# rapidshark-display-butt-mk-1_1.net
KiCad netlist of a schematic drawn in EAGLE
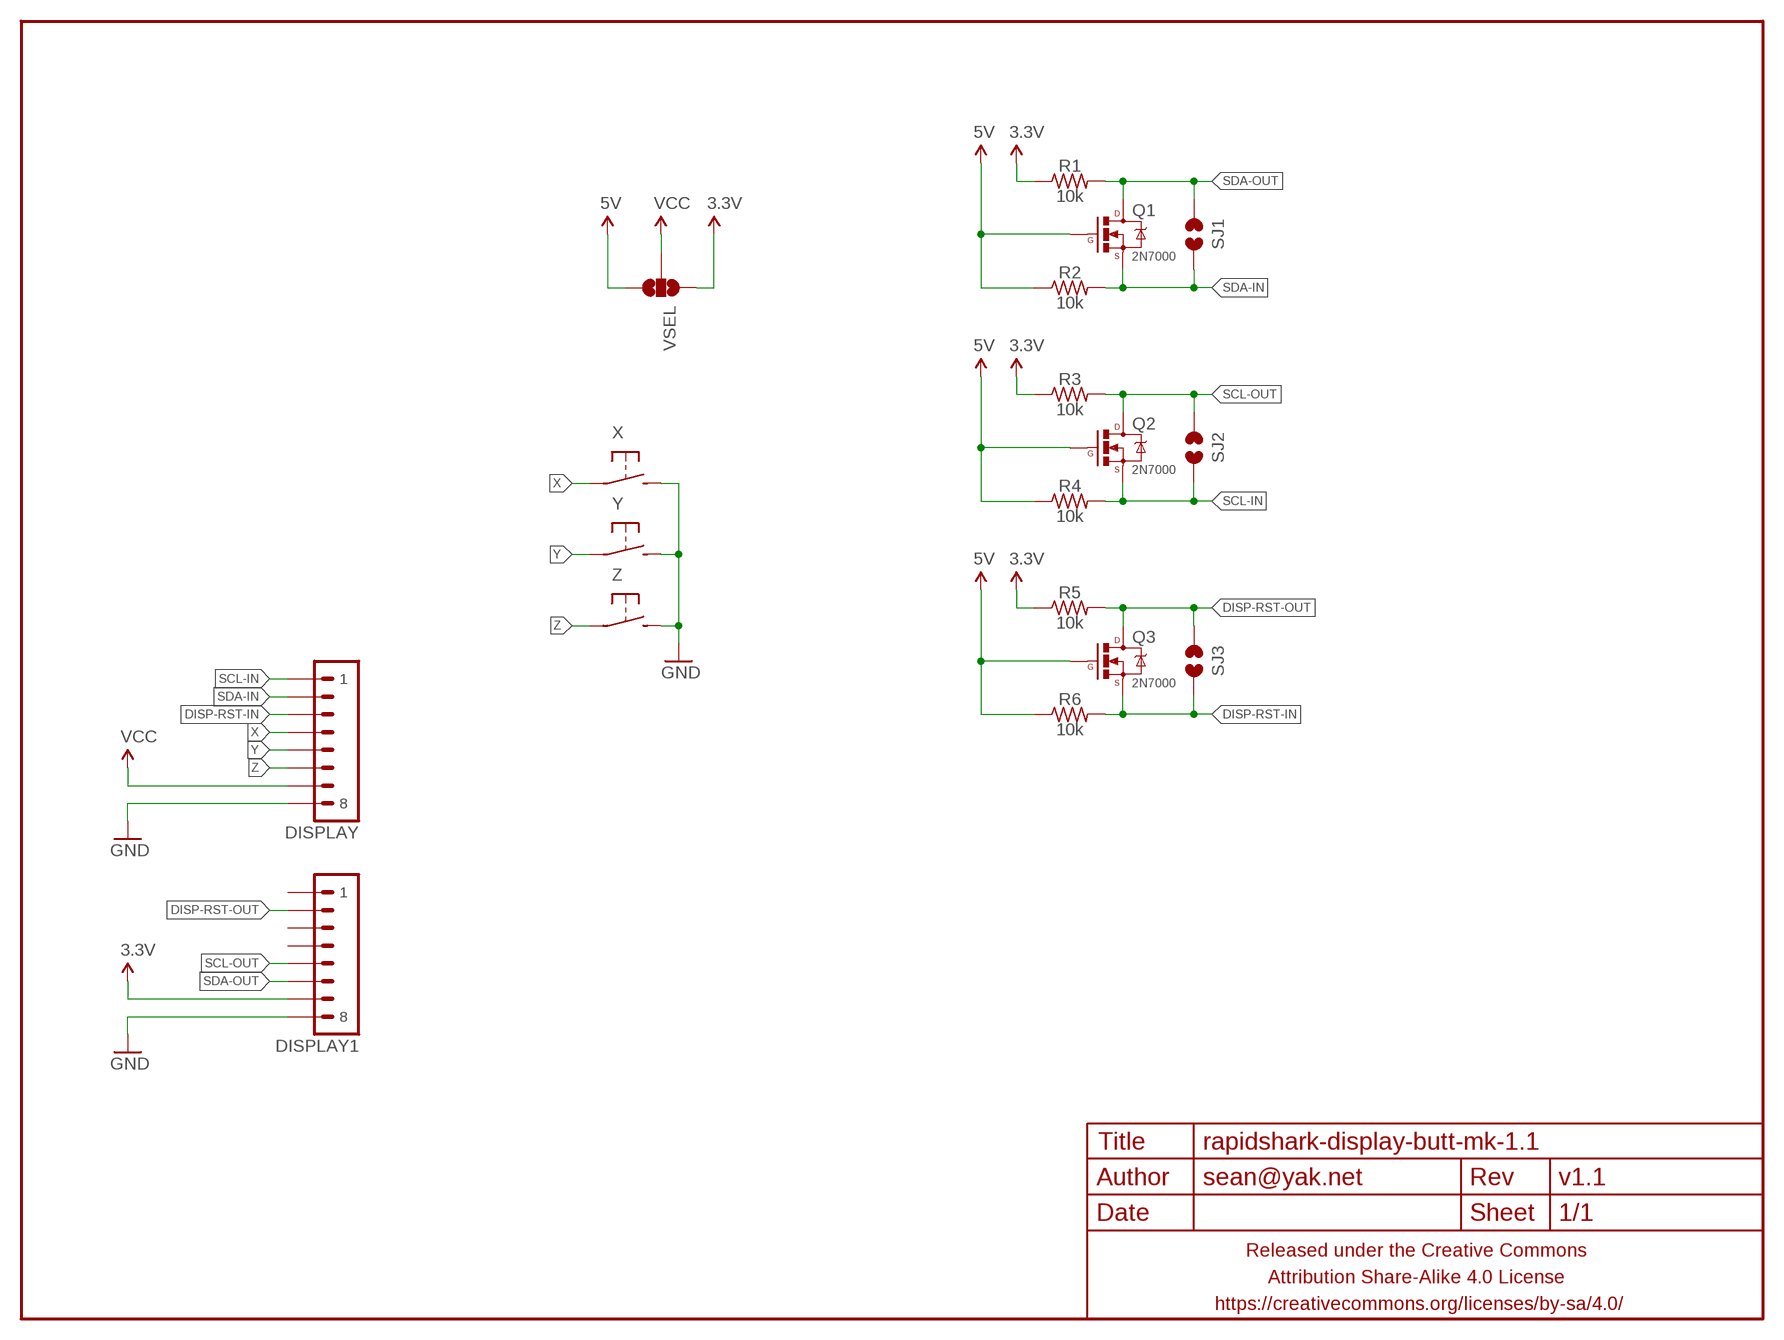
[diagram p0: schematic, sheet 1]

(export (version "E")
  (design (tool "Eeschema 10.0.6"))
  (components
    (comp (ref "DISPLAY")
      (value "M08JST-PH-VERT-PTH")
      (footprint "eagle-import:JST-8-VERT-PTH")
      (libsource (lib "eagle-import") (part "M08JST-PH-VERT-PTH"))
    )
    (comp (ref "DISPLAY1")
      (value "M081X08")
      (footprint "eagle-import:1X08")
      (libsource (lib "eagle-import") (part "M081X08"))
    )
    (comp (ref "FRAME1")
      (value "FRAME-LETTERNO_PACKAGE")
      (footprint "eagle-import:DUMMY")
      (fields (field (name "DESIGNER") "sean@yak.net") (field (name "VERSION") "v1.1"))
      (libsource (lib "eagle-import") (part "FRAME-LETTERNO_PACKAGE"))
    )
    (comp (ref "Q1")
      (value "2N7000")
      (footprint "eagle-import:TO-92-AMMO")
      (libsource (lib "eagle-import") (part "MOSFET-NCHANNEL2N7000-AMMO"))
    )
    (comp (ref "Q2")
      (value "2N7000")
      (footprint "eagle-import:TO-92-AMMO")
      (libsource (lib "eagle-import") (part "MOSFET-NCHANNEL2N7000-AMMO"))
    )
    (comp (ref "Q3")
      (value "2N7000")
      (footprint "eagle-import:TO-92-AMMO")
      (libsource (lib "eagle-import") (part "MOSFET-NCHANNEL2N7000-AMMO"))
    )
    (comp (ref "R1")
      (value "10k")
      (footprint "eagle-import:RESISTOR-AXIAL-PTH-5.08MM")
      (libsource (lib "eagle-import") (part "RESISTORPTH-AXIAL-5.08MM"))
    )
    (comp (ref "R2")
      (value "10k")
      (footprint "eagle-import:RESISTOR-AXIAL-PTH-5.08MM")
      (libsource (lib "eagle-import") (part "RESISTORPTH-AXIAL-5.08MM"))
    )
    (comp (ref "R3")
      (value "10k")
      (footprint "eagle-import:RESISTOR-AXIAL-PTH-5.08MM")
      (libsource (lib "eagle-import") (part "RESISTORPTH-AXIAL-5.08MM"))
    )
    (comp (ref "R4")
      (value "10k")
      (footprint "eagle-import:RESISTOR-AXIAL-PTH-5.08MM")
      (libsource (lib "eagle-import") (part "RESISTORPTH-AXIAL-5.08MM"))
    )
    (comp (ref "R5")
      (value "10k")
      (footprint "eagle-import:RESISTOR-AXIAL-PTH-5.08MM")
      (libsource (lib "eagle-import") (part "RESISTORPTH-AXIAL-5.08MM"))
    )
    (comp (ref "R6")
      (value "10k")
      (footprint "eagle-import:RESISTOR-AXIAL-PTH-5.08MM")
      (libsource (lib "eagle-import") (part "RESISTORPTH-AXIAL-5.08MM"))
    )
    (comp (ref "SJ1")
      (value "JUMPER-PAD-2-NOYES_SILK")
      (footprint "eagle-import:PAD-JUMPER-2-NO_YES_SILK")
      (libsource (lib "eagle-import") (part "JUMPER-PAD-2-NOYES_SILK"))
    )
    (comp (ref "SJ2")
      (value "JUMPER-PAD-2-NOYES_SILK")
      (footprint "eagle-import:PAD-JUMPER-2-NO_YES_SILK")
      (libsource (lib "eagle-import") (part "JUMPER-PAD-2-NOYES_SILK"))
    )
    (comp (ref "SJ3")
      (value "JUMPER-PAD-2-NOYES_SILK")
      (footprint "eagle-import:PAD-JUMPER-2-NO_YES_SILK")
      (libsource (lib "eagle-import") (part "JUMPER-PAD-2-NOYES_SILK"))
    )
    (comp (ref "VSEL")
      (value "JUMPER-PAD-3-NOFULL_BOX_SILK")
      (footprint "eagle-import:PAD-JUMPER-3-NO_YES_SILK_FULL_BOX")
      (libsource (lib "eagle-import") (part "JUMPER-PAD-3-NOFULL_BOX_SILK"))
    )
    (comp (ref "X")
      (value "SPST-NO-TACT6MM-PTH-SMALL-PADS")
      (footprint "eagle-import:DTS-6-SMALL-PADS")
      (libsource (lib "eagle-import") (part "SPST-NO-TACT6MM-PTH-SMALL-PADS"))
    )
    (comp (ref "Y")
      (value "SPST-NO-TACT6MM-PTH-SMALL-PADS")
      (footprint "eagle-import:DTS-6-SMALL-PADS")
      (libsource (lib "eagle-import") (part "SPST-NO-TACT6MM-PTH-SMALL-PADS"))
    )
    (comp (ref "Z")
      (value "SPST-NO-TACT6MM-PTH-SMALL-PADS")
      (footprint "eagle-import:DTS-6-SMALL-PADS")
      (libsource (lib "eagle-import") (part "SPST-NO-TACT6MM-PTH-SMALL-PADS"))
    )
  )
  (nets
    (net (code "1") (name "3.3V") (class "Default")
      (node (ref "DISPLAY1") (pin "7") (pinfunction "7_7") (pintype "passive"))
      (node (ref "R1") (pin "P$1") (pinfunction "1_P$1") (pintype "passive"))
      (node (ref "R3") (pin "P$1") (pinfunction "1_P$1") (pintype "passive"))
      (node (ref "R5") (pin "P$1") (pinfunction "1_P$1") (pintype "passive"))
      (node (ref "VSEL") (pin "1") (pinfunction "1_1") (pintype "passive"))
    )
    (net (code "2") (name "5V") (class "Default")
      (node (ref "Q1") (pin "2") (pinfunction "G_2") (pintype "passive"))
      (node (ref "Q2") (pin "2") (pinfunction "G_2") (pintype "passive"))
      (node (ref "Q3") (pin "2") (pinfunction "G_2") (pintype "passive"))
      (node (ref "R2") (pin "P$1") (pinfunction "1_P$1") (pintype "passive"))
      (node (ref "R4") (pin "P$1") (pinfunction "1_P$1") (pintype "passive"))
      (node (ref "R6") (pin "P$1") (pinfunction "1_P$1") (pintype "passive"))
      (node (ref "VSEL") (pin "3") (pinfunction "3_3") (pintype "passive"))
    )
    (net (code "3") (name "DISP-RST-IN") (class "Default")
      (node (ref "DISPLAY") (pin "3") (pinfunction "3_3") (pintype "passive"))
      (node (ref "Q3") (pin "1") (pinfunction "S_1") (pintype "passive"))
      (node (ref "R6") (pin "P$2") (pinfunction "2_P$2") (pintype "passive"))
      (node (ref "SJ3") (pin "1") (pinfunction "1_1") (pintype "passive"))
    )
    (net (code "4") (name "DISP-RST-OUT") (class "Default")
      (node (ref "DISPLAY1") (pin "2") (pinfunction "2_2") (pintype "passive"))
      (node (ref "Q3") (pin "3") (pinfunction "D_3") (pintype "passive"))
      (node (ref "R5") (pin "P$2") (pinfunction "2_P$2") (pintype "passive"))
      (node (ref "SJ3") (pin "2") (pinfunction "2_2") (pintype "passive"))
    )
    (net (code "5") (name "GND") (class "Default")
      (node (ref "DISPLAY") (pin "8") (pinfunction "8_8") (pintype "passive"))
      (node (ref "DISPLAY1") (pin "8") (pinfunction "8_8") (pintype "passive"))
      (node (ref "X") (pin "3") (pinfunction "2_3") (pintype "passive"))
      (node (ref "X") (pin "4") (pinfunction "2_4") (pintype "passive"))
      (node (ref "Y") (pin "3") (pinfunction "2_3") (pintype "passive"))
      (node (ref "Y") (pin "4") (pinfunction "2_4") (pintype "passive"))
      (node (ref "Z") (pin "3") (pinfunction "2_3") (pintype "passive"))
      (node (ref "Z") (pin "4") (pinfunction "2_4") (pintype "passive"))
    )
    (net (code "6") (name "SCL-IN") (class "Default")
      (node (ref "DISPLAY") (pin "1") (pinfunction "1_1") (pintype "passive"))
      (node (ref "Q2") (pin "1") (pinfunction "S_1") (pintype "passive"))
      (node (ref "R4") (pin "P$2") (pinfunction "2_P$2") (pintype "passive"))
      (node (ref "SJ2") (pin "1") (pinfunction "1_1") (pintype "passive"))
    )
    (net (code "7") (name "SCL-OUT") (class "Default")
      (node (ref "DISPLAY1") (pin "5") (pinfunction "5_5") (pintype "passive"))
      (node (ref "Q2") (pin "3") (pinfunction "D_3") (pintype "passive"))
      (node (ref "R3") (pin "P$2") (pinfunction "2_P$2") (pintype "passive"))
      (node (ref "SJ2") (pin "2") (pinfunction "2_2") (pintype "passive"))
    )
    (net (code "8") (name "SDA-IN") (class "Default")
      (node (ref "DISPLAY") (pin "2") (pinfunction "2_2") (pintype "passive"))
      (node (ref "Q1") (pin "1") (pinfunction "S_1") (pintype "passive"))
      (node (ref "R2") (pin "P$2") (pinfunction "2_P$2") (pintype "passive"))
      (node (ref "SJ1") (pin "1") (pinfunction "1_1") (pintype "passive"))
    )
    (net (code "9") (name "SDA-OUT") (class "Default")
      (node (ref "DISPLAY1") (pin "6") (pinfunction "6_6") (pintype "passive"))
      (node (ref "Q1") (pin "3") (pinfunction "D_3") (pintype "passive"))
      (node (ref "R1") (pin "P$2") (pinfunction "2_P$2") (pintype "passive"))
      (node (ref "SJ1") (pin "2") (pinfunction "2_2") (pintype "passive"))
    )
    (net (code "10") (name "VCC") (class "Default")
      (node (ref "DISPLAY") (pin "7") (pinfunction "7_7") (pintype "passive"))
      (node (ref "VSEL") (pin "2") (pinfunction "2_2") (pintype "passive"))
    )
    (net (code "11") (name "X") (class "Default")
      (node (ref "DISPLAY") (pin "4") (pinfunction "4_4") (pintype "passive"))
      (node (ref "X") (pin "1") (pinfunction "1_1") (pintype "passive"))
      (node (ref "X") (pin "2") (pinfunction "1_2") (pintype "passive"))
    )
    (net (code "12") (name "Y") (class "Default")
      (node (ref "DISPLAY") (pin "5") (pinfunction "5_5") (pintype "passive"))
      (node (ref "Y") (pin "1") (pinfunction "1_1") (pintype "passive"))
      (node (ref "Y") (pin "2") (pinfunction "1_2") (pintype "passive"))
    )
    (net (code "13") (name "Z") (class "Default")
      (node (ref "DISPLAY") (pin "6") (pinfunction "6_6") (pintype "passive"))
      (node (ref "Z") (pin "1") (pinfunction "1_1") (pintype "passive"))
      (node (ref "Z") (pin "2") (pinfunction "1_2") (pintype "passive"))
    )
    (net (code "14") (name "unconnected-(DISPLAY1-Pad1)") (class "Default")
      (node (ref "DISPLAY1") (pin "1") (pinfunction "1_1") (pintype "passive"))
    )
    (net (code "15") (name "unconnected-(DISPLAY1-Pad3)") (class "Default")
      (node (ref "DISPLAY1") (pin "3") (pinfunction "3_3") (pintype "passive"))
    )
    (net (code "16") (name "unconnected-(DISPLAY1-Pad4)") (class "Default")
      (node (ref "DISPLAY1") (pin "4") (pinfunction "4_4") (pintype "passive"))
    )
  )
)
